# main.net
KiCad netlist of a schematic drawn in Altium Designer
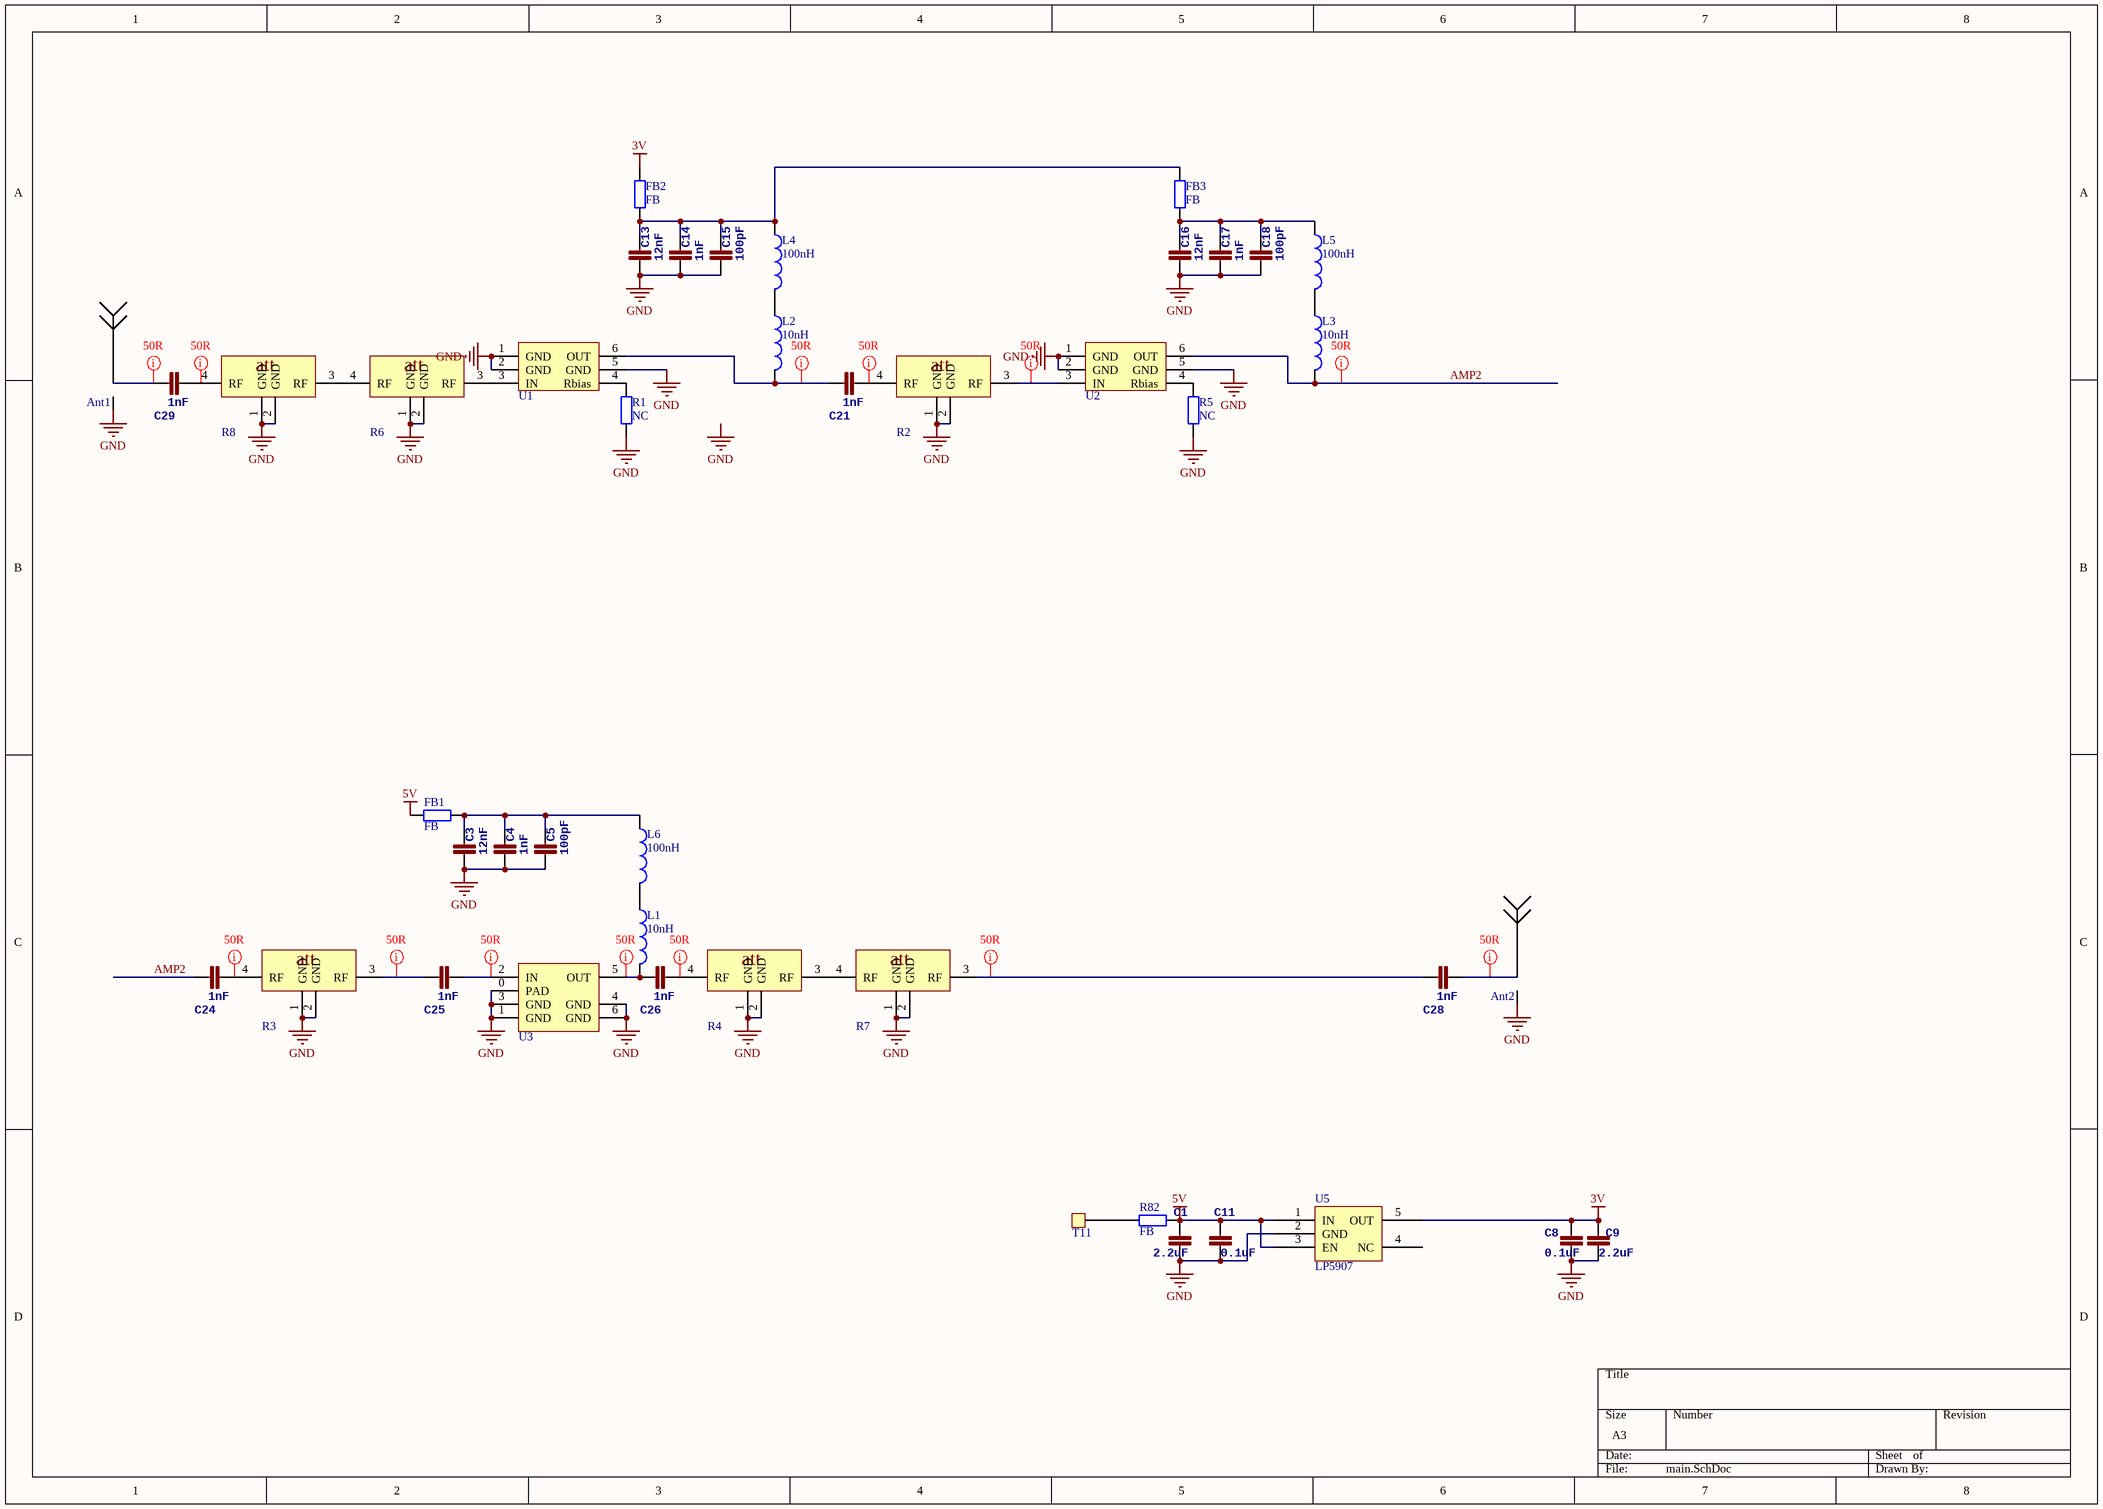
[diagram p0: main.SchDoc]

(export (version "E")
  (design (tool "Eeschema 10.0.6"))
  (components
    (comp (ref "Ant1") (value "Antenna") (footprint "SMA-2") (libsource (lib "F4SDR") (part "Antenna")))
    (comp (ref "Ant2") (value "Antenna") (footprint "SMA-2") (libsource (lib "F4SDR") (part "Antenna")))
    (comp (ref "C1")
      (value "2.2uF")
      (footprint "0603")
      (description "<b>Capacitor</b>\nStandard 0603 ceramic capacitor, and 0.1\" leaded capacitor.")
      (fields (field (name "PARTNO") "CC0402ZRY5V7BB104"))
      (libsource (lib "pixhawk2") (part "CAP0402-CAP"))
    )
    (comp (ref "C3")
      (value "12nF")
      (footprint "0805")
      (description "<b>Capacitor</b>\nStandard 0603 ceramic capacitor, and 0.1\" leaded capacitor.")
      (fields (field (name "PARTNO") "CC0402ZRY5V7BB104"))
      (libsource (lib "pixhawk2") (part "CAP0402-CAP"))
    )
    (comp (ref "C4")
      (value "1nF")
      (footprint "0402")
      (description "<b>Capacitor</b>\nStandard 0603 ceramic capacitor, and 0.1\" leaded capacitor.")
      (fields (field (name "PARTNO") "CC0402ZRY5V7BB104"))
      (libsource (lib "pixhawk2") (part "CAP0402-CAP"))
    )
    (comp (ref "C5")
      (value "100pF")
      (footprint "0402")
      (description "<b>Capacitor</b>\nStandard 0603 ceramic capacitor, and 0.1\" leaded capacitor.")
      (fields (field (name "PARTNO") "CC0402ZRY5V7BB104"))
      (libsource (lib "pixhawk2") (part "CAP0402-CAP"))
    )
    (comp (ref "C8")
      (value "0.1uF")
      (footprint "0603")
      (description "<b>Capacitor</b>\nStandard 0603 ceramic capacitor, and 0.1\" leaded capacitor.")
      (fields (field (name "PARTNO") "CC0402ZRY5V7BB104"))
      (libsource (lib "*") (part "CAP0402-CAP"))
    )
    (comp (ref "C9")
      (value "2.2uF")
      (footprint "0603")
      (description "<b>Capacitor</b>\nStandard 0603 ceramic capacitor, and 0.1\" leaded capacitor.")
      (fields (field (name "PARTNO") "CC0402ZRY5V7BB104"))
      (libsource (lib "pixhawk2") (part "CAP0402-CAP"))
    )
    (comp (ref "C11")
      (value "0.1uF")
      (footprint "0402")
      (description "<b>Capacitor</b>\nStandard 0603 ceramic capacitor, and 0.1\" leaded capacitor.")
      (fields (field (name "PARTNO") "CC0402ZRY5V7BB104"))
      (libsource (lib "*") (part "CAP0402-CAP"))
    )
    (comp (ref "C13")
      (value "12nF")
      (footprint "0805")
      (description "<b>Capacitor</b>\nStandard 0603 ceramic capacitor, and 0.1\" leaded capacitor.")
      (fields (field (name "PARTNO") "CC0402ZRY5V7BB104"))
      (libsource (lib "pixhawk2") (part "CAP0402-CAP"))
    )
    (comp (ref "C14")
      (value "1nF")
      (footprint "0402")
      (description "<b>Capacitor</b>\nStandard 0603 ceramic capacitor, and 0.1\" leaded capacitor.")
      (fields (field (name "PARTNO") "CC0402ZRY5V7BB104"))
      (libsource (lib "pixhawk2") (part "CAP0402-CAP"))
    )
    (comp (ref "C15")
      (value "100pF")
      (footprint "0402")
      (description "<b>Capacitor</b>\nStandard 0603 ceramic capacitor, and 0.1\" leaded capacitor.")
      (fields (field (name "PARTNO") "CC0402ZRY5V7BB104"))
      (libsource (lib "pixhawk2") (part "CAP0402-CAP"))
    )
    (comp (ref "C16")
      (value "12nF")
      (footprint "0805")
      (description "<b>Capacitor</b>\nStandard 0603 ceramic capacitor, and 0.1\" leaded capacitor.")
      (fields (field (name "PARTNO") "CC0402ZRY5V7BB104"))
      (libsource (lib "pixhawk2") (part "CAP0402-CAP"))
    )
    (comp (ref "C17")
      (value "1nF")
      (footprint "0402")
      (description "<b>Capacitor</b>\nStandard 0603 ceramic capacitor, and 0.1\" leaded capacitor.")
      (fields (field (name "PARTNO") "CC0402ZRY5V7BB104"))
      (libsource (lib "pixhawk2") (part "CAP0402-CAP"))
    )
    (comp (ref "C18")
      (value "100pF")
      (footprint "0402")
      (description "<b>Capacitor</b>\nStandard 0603 ceramic capacitor, and 0.1\" leaded capacitor.")
      (fields (field (name "PARTNO") "CC0402ZRY5V7BB104"))
      (libsource (lib "pixhawk2") (part "CAP0402-CAP"))
    )
    (comp (ref "C21")
      (value "1nF")
      (footprint "0402")
      (description "<b>Capacitor</b>\nStandard 0603 ceramic capacitor, and 0.1\" leaded capacitor.")
      (fields (field (name "PARTNO") "CC0402ZRY5V7BB104"))
      (libsource (lib "") (part "CAP0402-CAP_1"))
    )
    (comp (ref "C24")
      (value "1nF")
      (footprint "0402")
      (description "<b>Capacitor</b>\nStandard 0603 ceramic capacitor, and 0.1\" leaded capacitor.")
      (fields (field (name "PARTNO") "CC0402ZRY5V7BB104"))
      (libsource (lib "") (part "CAP0402-CAP_1"))
    )
    (comp (ref "C25")
      (value "1nF")
      (footprint "0402")
      (description "<b>Capacitor</b>\nStandard 0603 ceramic capacitor, and 0.1\" leaded capacitor.")
      (fields (field (name "PARTNO") "CC0402ZRY5V7BB104"))
      (libsource (lib "") (part "CAP0402-CAP_1"))
    )
    (comp (ref "C26")
      (value "1nF")
      (footprint "0402")
      (description "<b>Capacitor</b>\nStandard 0603 ceramic capacitor, and 0.1\" leaded capacitor.")
      (fields (field (name "PARTNO") "CC0402ZRY5V7BB104"))
      (libsource (lib "") (part "CAP0402-CAP_1"))
    )
    (comp (ref "C28")
      (value "1nF")
      (footprint "0402")
      (description "<b>Capacitor</b>\nStandard 0603 ceramic capacitor, and 0.1\" leaded capacitor.")
      (fields (field (name "PARTNO") "CC0402ZRY5V7BB104"))
      (libsource (lib "") (part "CAP0402-CAP_1"))
    )
    (comp (ref "C29")
      (value "1nF")
      (footprint "0402")
      (description "<b>Capacitor</b>\nStandard 0603 ceramic capacitor, and 0.1\" leaded capacitor.")
      (fields (field (name "PARTNO") "CC0402ZRY5V7BB104"))
      (libsource (lib "") (part "CAP0402-CAP_1"))
    )
    (comp (ref "FB1")
      (value "FB")
      (footprint "0603")
      (description "Resistor")
      (fields (field (name "PUBLISHER") "Altium Limited"))
      (libsource (lib "") (part "Res2_1"))
    )
    (comp (ref "FB2")
      (value "FB")
      (footprint "0603")
      (description "Resistor")
      (fields (field (name "PUBLISHER") "Altium Limited"))
      (libsource (lib "Miscellaneous Devices") (part "Res2"))
    )
    (comp (ref "FB3")
      (value "FB")
      (footprint "0603")
      (description "Resistor")
      (fields (field (name "PUBLISHER") "Altium Limited"))
      (libsource (lib "Miscellaneous Devices") (part "Res2"))
    )
    (comp (ref "L1")
      (value "10nH")
      (footprint "0402")
      (description "Inductor")
      (fields (field (name "PUBLISHER") "Altium Limited"))
      (libsource (lib "Miscellaneous Devices") (part "Inductor"))
    )
    (comp (ref "L2")
      (value "10nH")
      (footprint "0402")
      (description "Inductor")
      (fields (field (name "PUBLISHER") "Altium Limited"))
      (libsource (lib "Miscellaneous Devices") (part "Inductor"))
    )
    (comp (ref "L3")
      (value "10nH")
      (footprint "0402")
      (description "Inductor")
      (fields (field (name "PUBLISHER") "Altium Limited"))
      (libsource (lib "Miscellaneous Devices") (part "Inductor"))
    )
    (comp (ref "L4")
      (value "100nH")
      (footprint "0603L")
      (description "Inductor")
      (fields (field (name "PUBLISHER") "Altium Limited"))
      (libsource (lib "Miscellaneous Devices") (part "Inductor"))
    )
    (comp (ref "L5")
      (value "100nH")
      (footprint "0603L")
      (description "Inductor")
      (fields (field (name "PUBLISHER") "Altium Limited"))
      (libsource (lib "Miscellaneous Devices") (part "Inductor"))
    )
    (comp (ref "L6")
      (value "100nH")
      (footprint "0603L")
      (description "Inductor")
      (fields (field (name "PUBLISHER") "Altium Limited"))
      (libsource (lib "Miscellaneous Devices") (part "Inductor"))
    )
    (comp (ref "R1")
      (value "NC")
      (footprint "0402")
      (description "Resistor")
      (fields (field (name "PUBLISHER") "Altium Limited"))
      (libsource (lib "Miscellaneous Devices") (part "Res2"))
    )
    (comp (ref "R2")
      (value "EXB24-RF-ATT")
      (footprint "EXB24AT-RF-ATT")
      (libsource (lib "F4SDR") (part "EXB24-RF-ATT"))
    )
    (comp (ref "R3")
      (value "EXB24-RF-ATT")
      (footprint "EXB24AT-RF-ATT")
      (libsource (lib "F4SDR") (part "EXB24-RF-ATT"))
    )
    (comp (ref "R4")
      (value "EXB24-RF-ATT")
      (footprint "EXB24AT-RF-ATT")
      (libsource (lib "F4SDR") (part "EXB24-RF-ATT"))
    )
    (comp (ref "R5")
      (value "NC")
      (footprint "0402")
      (description "Resistor")
      (fields (field (name "PUBLISHER") "Altium Limited"))
      (libsource (lib "Miscellaneous Devices") (part "Res2"))
    )
    (comp (ref "R6")
      (value "EXB24-RF-ATT")
      (footprint "EXB24AT-RF-ATT")
      (libsource (lib "F4SDR") (part "EXB24-RF-ATT"))
    )
    (comp (ref "R7")
      (value "EXB24-RF-ATT")
      (footprint "EXB24AT-RF-ATT")
      (libsource (lib "F4SDR") (part "EXB24-RF-ATT"))
    )
    (comp (ref "R8")
      (value "EXB24-RF-ATT")
      (footprint "EXB24AT-RF-ATT")
      (libsource (lib "F4SDR") (part "EXB24-RF-ATT"))
    )
    (comp (ref "R82")
      (value "FB")
      (footprint "0603L")
      (description "Resistor")
      (fields (field (name "PUBLISHER") "Altium Limited"))
      (libsource (lib "") (part "Res2_2"))
    )
    (comp (ref "T11") (value "TestPad") (footprint "TestPad - 1mm") (libsource (lib "sch") (part "TestPad")))
    (comp (ref "U1") (value "MGA85563") (footprint "SC-70-6") (libsource (lib "F4SDR") (part "MGA85563")))
    (comp (ref "U2") (value "MGA85563") (footprint "SC-70-6") (libsource (lib "F4SDR") (part "MGA85563")))
    (comp (ref "U3") (value "HMC788") (footprint "HMC788") (libsource (lib "F4SDR") (part "HMC788")))
    (comp (ref "U5") (value "LP5907") (footprint "SOT23-5") (libsource (lib "RTC6705") (part "LP5907")))
  )
  (nets
    (net (code "1") (name "/AMP2") (class "Default")
      (node (ref "C24") (pin "1") (pinfunction "1_1") (pintype "passive"))
      (node (ref "L3") (pin "2") (pinfunction "2_2") (pintype "passive"))
      (node (ref "U2") (pin "6") (pinfunction "OUT_6") (pintype "passive"))
    )
    (net (code "2") (name "3V") (class "Default")
      (node (ref "C8") (pin "2") (pinfunction "2_2") (pintype "passive"))
      (node (ref "C9") (pin "2") (pinfunction "2_2") (pintype "passive"))
      (node (ref "FB2") (pin "2") (pinfunction "2_2") (pintype "passive"))
      (node (ref "U5") (pin "5") (pinfunction "OUT_5") (pintype "passive"))
    )
    (net (code "3") (name "5V") (class "Default")
      (node (ref "C1") (pin "2") (pinfunction "2_2") (pintype "passive"))
      (node (ref "C11") (pin "2") (pinfunction "2_2") (pintype "passive"))
      (node (ref "FB1") (pin "1") (pinfunction "1_1") (pintype "passive"))
      (node (ref "R82") (pin "1") (pinfunction "1_1") (pintype "passive"))
      (node (ref "U5") (pin "1") (pinfunction "IN_1") (pintype "passive"))
      (node (ref "U5") (pin "3") (pinfunction "EN_3") (pintype "passive"))
    )
    (net (code "4") (name "GND") (class "Default")
      (node (ref "Ant1") (pin "GND") (pinfunction "G_GND") (pintype "passive"))
      (node (ref "Ant2") (pin "GND") (pinfunction "G_GND") (pintype "passive"))
      (node (ref "C1") (pin "1") (pinfunction "1_1") (pintype "passive"))
      (node (ref "C11") (pin "1") (pinfunction "1_1") (pintype "passive"))
      (node (ref "C13") (pin "1") (pinfunction "1_1") (pintype "passive"))
      (node (ref "C14") (pin "1") (pinfunction "1_1") (pintype "passive"))
      (node (ref "C15") (pin "1") (pinfunction "1_1") (pintype "passive"))
      (node (ref "C16") (pin "1") (pinfunction "1_1") (pintype "passive"))
      (node (ref "C17") (pin "1") (pinfunction "1_1") (pintype "passive"))
      (node (ref "C18") (pin "1") (pinfunction "1_1") (pintype "passive"))
      (node (ref "C3") (pin "1") (pinfunction "1_1") (pintype "passive"))
      (node (ref "C4") (pin "1") (pinfunction "1_1") (pintype "passive"))
      (node (ref "C5") (pin "1") (pinfunction "1_1") (pintype "passive"))
      (node (ref "C8") (pin "1") (pinfunction "1_1") (pintype "passive"))
      (node (ref "C9") (pin "1") (pinfunction "1_1") (pintype "passive"))
      (node (ref "R1") (pin "1") (pinfunction "1_1") (pintype "passive"))
      (node (ref "R2") (pin "1") (pinfunction "GND_1") (pintype "passive"))
      (node (ref "R2") (pin "2") (pinfunction "GND_2") (pintype "passive"))
      (node (ref "R3") (pin "1") (pinfunction "GND_1") (pintype "passive"))
      (node (ref "R3") (pin "2") (pinfunction "GND_2") (pintype "passive"))
      (node (ref "R4") (pin "1") (pinfunction "GND_1") (pintype "passive"))
      (node (ref "R4") (pin "2") (pinfunction "GND_2") (pintype "passive"))
      (node (ref "R5") (pin "1") (pinfunction "1_1") (pintype "passive"))
      (node (ref "R6") (pin "1") (pinfunction "GND_1") (pintype "passive"))
      (node (ref "R6") (pin "2") (pinfunction "GND_2") (pintype "passive"))
      (node (ref "R7") (pin "1") (pinfunction "GND_1") (pintype "passive"))
      (node (ref "R7") (pin "2") (pinfunction "GND_2") (pintype "passive"))
      (node (ref "R8") (pin "1") (pinfunction "GND_1") (pintype "passive"))
      (node (ref "R8") (pin "2") (pinfunction "GND_2") (pintype "passive"))
      (node (ref "U1") (pin "1") (pinfunction "GND_1") (pintype "passive"))
      (node (ref "U1") (pin "2") (pinfunction "GND_2") (pintype "passive"))
      (node (ref "U1") (pin "5") (pinfunction "GND_5") (pintype "passive"))
      (node (ref "U2") (pin "1") (pinfunction "GND_1") (pintype "passive"))
      (node (ref "U2") (pin "2") (pinfunction "GND_2") (pintype "passive"))
      (node (ref "U2") (pin "5") (pinfunction "GND_5") (pintype "passive"))
      (node (ref "U3") (pin "0") (pinfunction "PAD_0") (pintype "passive"))
      (node (ref "U3") (pin "1") (pinfunction "GND_1") (pintype "passive"))
      (node (ref "U3") (pin "3") (pinfunction "GND_3") (pintype "passive"))
      (node (ref "U3") (pin "4") (pinfunction "GND_4") (pintype "passive"))
      (node (ref "U3") (pin "6") (pinfunction "GND_6") (pintype "passive"))
      (node (ref "U5") (pin "2") (pinfunction "GND_2") (pintype "passive"))
    )
    (net (code "5") (name "Net-(Ant1-Pad1)") (class "Default")
      (node (ref "Ant1") (pin "1") (pinfunction "1_1") (pintype "passive"))
      (node (ref "C29") (pin "1") (pinfunction "1_1") (pintype "passive"))
    )
    (net (code "6") (name "Net-(Ant2-Pad1)") (class "Default")
      (node (ref "Ant2") (pin "1") (pinfunction "1_1") (pintype "passive"))
      (node (ref "C28") (pin "2") (pinfunction "2_2") (pintype "passive"))
    )
    (net (code "7") (name "Net-(C3-Pad2)") (class "Default")
      (node (ref "C3") (pin "2") (pinfunction "2_2") (pintype "passive"))
      (node (ref "C4") (pin "2") (pinfunction "2_2") (pintype "passive"))
      (node (ref "C5") (pin "2") (pinfunction "2_2") (pintype "passive"))
      (node (ref "FB1") (pin "2") (pinfunction "2_2") (pintype "passive"))
      (node (ref "L6") (pin "1") (pinfunction "1_1") (pintype "passive"))
    )
    (net (code "8") (name "Net-(C13-Pad2)") (class "Default")
      (node (ref "C13") (pin "2") (pinfunction "2_2") (pintype "passive"))
      (node (ref "C14") (pin "2") (pinfunction "2_2") (pintype "passive"))
      (node (ref "C15") (pin "2") (pinfunction "2_2") (pintype "passive"))
      (node (ref "FB2") (pin "1") (pinfunction "1_1") (pintype "passive"))
      (node (ref "FB3") (pin "2") (pinfunction "2_2") (pintype "passive"))
      (node (ref "L4") (pin "1") (pinfunction "1_1") (pintype "passive"))
    )
    (net (code "9") (name "Net-(C16-Pad2)") (class "Default")
      (node (ref "C16") (pin "2") (pinfunction "2_2") (pintype "passive"))
      (node (ref "C17") (pin "2") (pinfunction "2_2") (pintype "passive"))
      (node (ref "C18") (pin "2") (pinfunction "2_2") (pintype "passive"))
      (node (ref "FB3") (pin "1") (pinfunction "1_1") (pintype "passive"))
      (node (ref "L5") (pin "1") (pinfunction "1_1") (pintype "passive"))
    )
    (net (code "10") (name "Net-(C21-Pad2)") (class "Default")
      (node (ref "C21") (pin "2") (pinfunction "2_2") (pintype "passive"))
      (node (ref "R2") (pin "4") (pinfunction "RF_4") (pintype "passive"))
    )
    (net (code "11") (name "Net-(C24-Pad2)") (class "Default")
      (node (ref "C24") (pin "2") (pinfunction "2_2") (pintype "passive"))
      (node (ref "R3") (pin "4") (pinfunction "RF_4") (pintype "passive"))
    )
    (net (code "12") (name "Net-(C25-Pad1)") (class "Default")
      (node (ref "C25") (pin "1") (pinfunction "1_1") (pintype "passive"))
      (node (ref "R3") (pin "3") (pinfunction "RF_3") (pintype "passive"))
    )
    (net (code "13") (name "Net-(C26-Pad2)") (class "Default")
      (node (ref "C26") (pin "2") (pinfunction "2_2") (pintype "passive"))
      (node (ref "R4") (pin "4") (pinfunction "RF_4") (pintype "passive"))
    )
    (net (code "14") (name "Net-(C28-Pad1)") (class "Default")
      (node (ref "C28") (pin "1") (pinfunction "1_1") (pintype "passive"))
      (node (ref "R7") (pin "3") (pinfunction "RF_3") (pintype "passive"))
    )
    (net (code "15") (name "Net-(C29-Pad2)") (class "Default")
      (node (ref "C29") (pin "2") (pinfunction "2_2") (pintype "passive"))
      (node (ref "R8") (pin "4") (pinfunction "RF_4") (pintype "passive"))
    )
    (net (code "16") (name "Net-(L1-Pad1)") (class "Default")
      (node (ref "L1") (pin "1") (pinfunction "1_1") (pintype "passive"))
      (node (ref "L6") (pin "2") (pinfunction "2_2") (pintype "passive"))
    )
    (net (code "17") (name "Net-(L2-Pad1)") (class "Default")
      (node (ref "L2") (pin "1") (pinfunction "1_1") (pintype "passive"))
      (node (ref "L4") (pin "2") (pinfunction "2_2") (pintype "passive"))
    )
    (net (code "18") (name "Net-(L3-Pad1)") (class "Default")
      (node (ref "L3") (pin "1") (pinfunction "1_1") (pintype "passive"))
      (node (ref "L5") (pin "2") (pinfunction "2_2") (pintype "passive"))
    )
    (net (code "19") (name "Net-(R4-RF-Pad3)") (class "Default")
      (node (ref "R4") (pin "3") (pinfunction "RF_3") (pintype "passive"))
      (node (ref "R7") (pin "4") (pinfunction "RF_4") (pintype "passive"))
    )
    (net (code "20") (name "Net-(R6-RF-Pad4)") (class "Default")
      (node (ref "R6") (pin "4") (pinfunction "RF_4") (pintype "passive"))
      (node (ref "R8") (pin "3") (pinfunction "RF_3") (pintype "passive"))
    )
    (net (code "21") (name "Net-(T11-3)") (class "Default")
      (node (ref "R82") (pin "2") (pinfunction "2_2") (pintype "passive"))
      (node (ref "T11") (pin "1") (pinfunction "3_1") (pintype "passive"))
    )
    (net (code "22") (name "Net-(U1-IN)") (class "Default")
      (node (ref "R6") (pin "3") (pinfunction "RF_3") (pintype "passive"))
      (node (ref "U1") (pin "3") (pinfunction "IN_3") (pintype "passive"))
    )
    (net (code "23") (name "Net-(U1-OUT)") (class "Default")
      (node (ref "C21") (pin "1") (pinfunction "1_1") (pintype "passive"))
      (node (ref "L2") (pin "2") (pinfunction "2_2") (pintype "passive"))
      (node (ref "U1") (pin "6") (pinfunction "OUT_6") (pintype "passive"))
    )
    (net (code "24") (name "Net-(U1-Rbias)") (class "Default")
      (node (ref "R1") (pin "2") (pinfunction "2_2") (pintype "passive"))
      (node (ref "U1") (pin "4") (pinfunction "Rbias_4") (pintype "passive"))
    )
    (net (code "25") (name "Net-(U2-IN)") (class "Default")
      (node (ref "R2") (pin "3") (pinfunction "RF_3") (pintype "passive"))
      (node (ref "U2") (pin "3") (pinfunction "IN_3") (pintype "passive"))
    )
    (net (code "26") (name "Net-(U2-Rbias)") (class "Default")
      (node (ref "R5") (pin "2") (pinfunction "2_2") (pintype "passive"))
      (node (ref "U2") (pin "4") (pinfunction "Rbias_4") (pintype "passive"))
    )
    (net (code "27") (name "Net-(U3-IN)") (class "Default")
      (node (ref "C25") (pin "2") (pinfunction "2_2") (pintype "passive"))
      (node (ref "U3") (pin "2") (pinfunction "IN_2") (pintype "passive"))
    )
    (net (code "28") (name "Net-(U3-OUT)") (class "Default")
      (node (ref "C26") (pin "1") (pinfunction "1_1") (pintype "passive"))
      (node (ref "L1") (pin "2") (pinfunction "2_2") (pintype "passive"))
      (node (ref "U3") (pin "5") (pinfunction "OUT_5") (pintype "passive"))
    )
    (net (code "29") (name "unconnected-(U5-NC-Pad4)") (class "Default")
      (node (ref "U5") (pin "4") (pinfunction "NC_4") (pintype "passive"))
    )
  )
)
